# PinConnector.net
KiCad netlist of a schematic drawn in Altium Designer
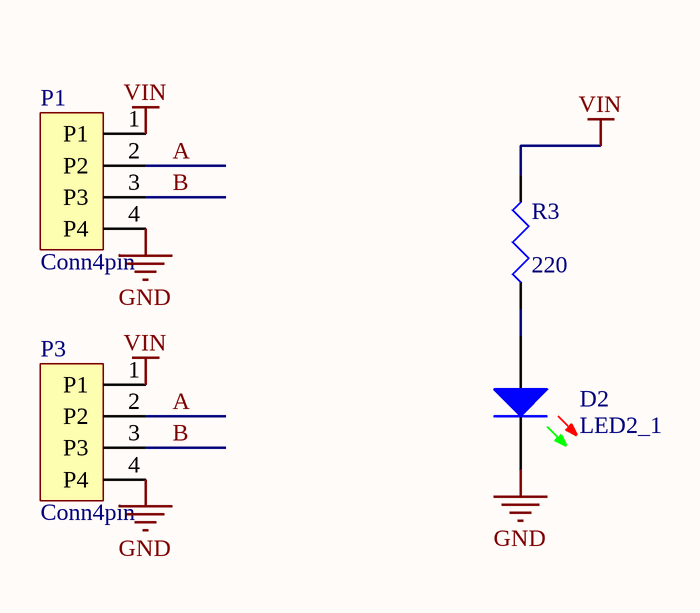
[diagram p0: PinConnector.SchDoc]

(export (version "E")
  (design (tool "Eeschema 10.0.6"))
  (components
    (comp (ref "D2")
      (value "LED2_1")
      (footprint "LED0603")
      (description "Typical RED, GREEN, YELLOW, AMBER GaAs LED")
      (fields (field (name "PUBLISHER") "Altium Limited"))
      (libsource (lib "SenaCorpLibSCH") (part "LED2_1"))
    )
    (comp (ref "P1")
      (value "Conn4pin")
      (footprint "Bourns 70AB/Female (4 conn)")
      (libsource (lib "SenaCorpLibSCH") (part "Conn4pin"))
    )
    (comp (ref "P3")
      (value "Conn4pin")
      (footprint "Connector 4pin 75mil space")
      (libsource (lib "SenaCorpLibSCH") (part "Conn4pin"))
    )
    (comp (ref "R3")
      (value "220")
      (footprint "0603")
      (description "Resistor")
      (fields (field (name "PUBLISHER") "Altium Limited"))
      (libsource (lib "SenaCorpLibSCH") (part "Res3"))
    )
  )
  (nets
    (net (code "1") (name "/A") (class "Default")
      (node (ref "P1") (pin "2") (pinfunction "P2_2") (pintype "passive"))
      (node (ref "P3") (pin "2") (pinfunction "P2_2") (pintype "passive"))
    )
    (net (code "2") (name "/B") (class "Default")
      (node (ref "P1") (pin "3") (pinfunction "P3_3") (pintype "passive"))
      (node (ref "P3") (pin "3") (pinfunction "P3_3") (pintype "passive"))
    )
    (net (code "3") (name "GND") (class "Default")
      (node (ref "D2") (pin "2") (pinfunction "K_2") (pintype "passive"))
      (node (ref "P1") (pin "4") (pinfunction "P4_4") (pintype "passive"))
      (node (ref "P3") (pin "4") (pinfunction "P4_4") (pintype "passive"))
    )
    (net (code "4") (name "Net-(D2-A)") (class "Default")
      (node (ref "D2") (pin "1") (pinfunction "A_1") (pintype "passive"))
      (node (ref "R3") (pin "1") (pinfunction "1_1") (pintype "passive"))
    )
    (net (code "5") (name "VIN") (class "Default")
      (node (ref "P1") (pin "1") (pinfunction "P1_1") (pintype "passive"))
      (node (ref "P3") (pin "1") (pinfunction "P1_1") (pintype "passive"))
      (node (ref "R3") (pin "2") (pinfunction "2_2") (pintype "passive"))
    )
  )
)
